# MiniDice.net
KiCad netlist of a schematic drawn in EAGLE
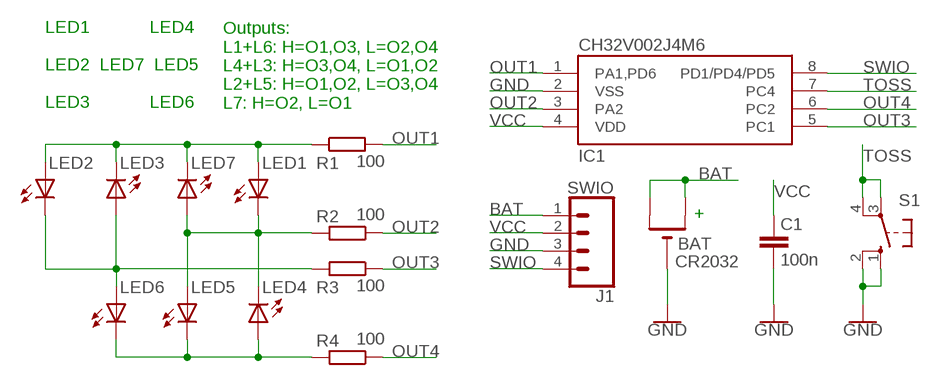
[diagram p0: schematic, sheet 1]

(export (version "E")
  (design (tool "Eeschema 10.0.6"))
  (components
    (comp (ref "BAT")
      (value "CR2032")
      (footprint "eagle-import:CR2032-SMD")
      (libsource (lib "eagle-import") (part "CR2032SMT"))
    )
    (comp (ref "C1")
      (value "100n")
      (footprint "eagle-import:C1206K")
      (libsource (lib "eagle-import") (part "C-EUC1206K"))
    )
    (comp (ref "IC1")
      (value "CH32V002J4M6")
      (footprint "eagle-import:SOP8")
      (libsource (lib "eagle-import") (part "CH32V003J4M6"))
    )
    (comp (ref "J1")
      (value "SWIO")
      (footprint "eagle-import:1X04_SMD_LONG")
      (libsource (lib "eagle-import") (part "CONN_04SMD_LONG"))
    )
    (comp (ref "LED1")
      (value "LEDLED5MMB")
      (footprint "eagle-import:LED5MMB")
      (libsource (lib "eagle-import") (part "LEDLED5MMB"))
    )
    (comp (ref "LED2")
      (value "LEDLED5MMB")
      (footprint "eagle-import:LED5MMB")
      (libsource (lib "eagle-import") (part "LEDLED5MMB"))
    )
    (comp (ref "LED3")
      (value "LEDLED5MMB")
      (footprint "eagle-import:LED5MMB")
      (libsource (lib "eagle-import") (part "LEDLED5MMB"))
    )
    (comp (ref "LED4")
      (value "LEDLED5MMB")
      (footprint "eagle-import:LED5MMB")
      (libsource (lib "eagle-import") (part "LEDLED5MMB"))
    )
    (comp (ref "LED5")
      (value "LEDLED5MMB")
      (footprint "eagle-import:LED5MMB")
      (libsource (lib "eagle-import") (part "LEDLED5MMB"))
    )
    (comp (ref "LED6")
      (value "LEDLED5MMB")
      (footprint "eagle-import:LED5MMB")
      (libsource (lib "eagle-import") (part "LEDLED5MMB"))
    )
    (comp (ref "LED7")
      (value "LEDLED5MMB")
      (footprint "eagle-import:LED5MMB")
      (libsource (lib "eagle-import") (part "LEDLED5MMB"))
    )
    (comp (ref "R1")
      (value "100")
      (footprint "eagle-import:M1206")
      (libsource (lib "eagle-import") (part "R-EU_M1206"))
    )
    (comp (ref "R2")
      (value "100")
      (footprint "eagle-import:M1206")
      (libsource (lib "eagle-import") (part "R-EU_M1206"))
    )
    (comp (ref "R3")
      (value "100")
      (footprint "eagle-import:M1206")
      (libsource (lib "eagle-import") (part "R-EU_M1206"))
    )
    (comp (ref "R4")
      (value "100")
      (footprint "eagle-import:M1206")
      (libsource (lib "eagle-import") (part "R-EU_M1206"))
    )
    (comp (ref "S1")
      (value "10-XXB3F-10XXSMD")
      (footprint "eagle-import:B3F-10XXSMD")
      (libsource (lib "eagle-import") (part "10-XXB3F-10XXSMD"))
    )
  )
  (nets
    (net (code "1") (name "/BAT") (class "Default")
      (node (ref "BAT") (pin "+$1") (pinfunction "+_+$1") (pintype "passive"))
      (node (ref "BAT") (pin "+$2") (pinfunction "+1_+$2") (pintype "passive"))
      (node (ref "J1") (pin "1") (pinfunction "1_1") (pintype "passive"))
    )
    (net (code "2") (name "/OUT1") (class "Default")
      (node (ref "IC1") (pin "1") (pinfunction "PA1,PD6_1") (pintype "bidirectional"))
      (node (ref "R1") (pin "2") (pinfunction "2_2") (pintype "passive"))
    )
    (net (code "3") (name "/OUT2") (class "Default")
      (node (ref "IC1") (pin "3") (pinfunction "PA2_3") (pintype "bidirectional"))
      (node (ref "R2") (pin "1") (pinfunction "1_1") (pintype "passive"))
    )
    (net (code "4") (name "/OUT3") (class "Default")
      (node (ref "IC1") (pin "5") (pinfunction "PC1_5") (pintype "bidirectional"))
      (node (ref "R3") (pin "1") (pinfunction "1_1") (pintype "passive"))
    )
    (net (code "5") (name "/OUT4") (class "Default")
      (node (ref "IC1") (pin "6") (pinfunction "PC2_6") (pintype "bidirectional"))
      (node (ref "R4") (pin "1") (pinfunction "1_1") (pintype "passive"))
    )
    (net (code "6") (name "/SWIO") (class "Default")
      (node (ref "IC1") (pin "8") (pinfunction "PD1/PD4/PD5_8") (pintype "bidirectional"))
      (node (ref "J1") (pin "4") (pinfunction "4_4") (pintype "passive"))
    )
    (net (code "7") (name "/TOSS") (class "Default")
      (node (ref "IC1") (pin "7") (pinfunction "PC4_7") (pintype "bidirectional"))
      (node (ref "S1") (pin "3") (pinfunction "P_3") (pintype "passive"))
      (node (ref "S1") (pin "4") (pinfunction "P1_4") (pintype "passive"))
    )
    (net (code "8") (name "/VCC") (class "Default")
      (node (ref "C1") (pin "1") (pinfunction "1_1") (pintype "passive"))
      (node (ref "IC1") (pin "4") (pinfunction "VDD_4") (pintype "power_in"))
      (node (ref "J1") (pin "2") (pinfunction "2_2") (pintype "passive"))
    )
    (net (code "9") (name "GND") (class "Default")
      (node (ref "BAT") (pin "-") (pinfunction "-_-") (pintype "passive"))
      (node (ref "C1") (pin "2") (pinfunction "2_2") (pintype "passive"))
      (node (ref "IC1") (pin "2") (pinfunction "VSS_2") (pintype "power_in"))
      (node (ref "J1") (pin "3") (pinfunction "3_3") (pintype "passive"))
      (node (ref "S1") (pin "1") (pinfunction "S_1") (pintype "passive"))
      (node (ref "S1") (pin "2") (pinfunction "S1_2") (pintype "passive"))
    )
    (net (code "10") (name "Net-(LED1-C)") (class "Default")
      (node (ref "LED1") (pin "K") (pinfunction "C_K") (pintype "passive"))
      (node (ref "LED4") (pin "K") (pinfunction "C_K") (pintype "passive"))
      (node (ref "LED5") (pin "A") (pinfunction "A_A") (pintype "passive"))
      (node (ref "LED7") (pin "A") (pinfunction "A_A") (pintype "passive"))
      (node (ref "R2") (pin "2") (pinfunction "2_2") (pintype "passive"))
    )
    (net (code "11") (name "Net-(LED2-C)") (class "Default")
      (node (ref "LED2") (pin "K") (pinfunction "C_K") (pintype "passive"))
      (node (ref "LED3") (pin "A") (pinfunction "A_A") (pintype "passive"))
      (node (ref "LED6") (pin "A") (pinfunction "A_A") (pintype "passive"))
      (node (ref "R3") (pin "2") (pinfunction "2_2") (pintype "passive"))
    )
    (net (code "12") (name "Net-(LED3-C)") (class "Default")
      (node (ref "LED1") (pin "A") (pinfunction "A_A") (pintype "passive"))
      (node (ref "LED2") (pin "A") (pinfunction "A_A") (pintype "passive"))
      (node (ref "LED3") (pin "K") (pinfunction "C_K") (pintype "passive"))
      (node (ref "LED7") (pin "K") (pinfunction "C_K") (pintype "passive"))
      (node (ref "R1") (pin "1") (pinfunction "1_1") (pintype "passive"))
    )
    (net (code "13") (name "Net-(LED5-C)") (class "Default")
      (node (ref "LED4") (pin "A") (pinfunction "A_A") (pintype "passive"))
      (node (ref "LED5") (pin "K") (pinfunction "C_K") (pintype "passive"))
      (node (ref "LED6") (pin "K") (pinfunction "C_K") (pintype "passive"))
      (node (ref "R4") (pin "2") (pinfunction "2_2") (pintype "passive"))
    )
  )
)
